# 11_DDR2.net
KiCad netlist of a schematic drawn in Altium Designer
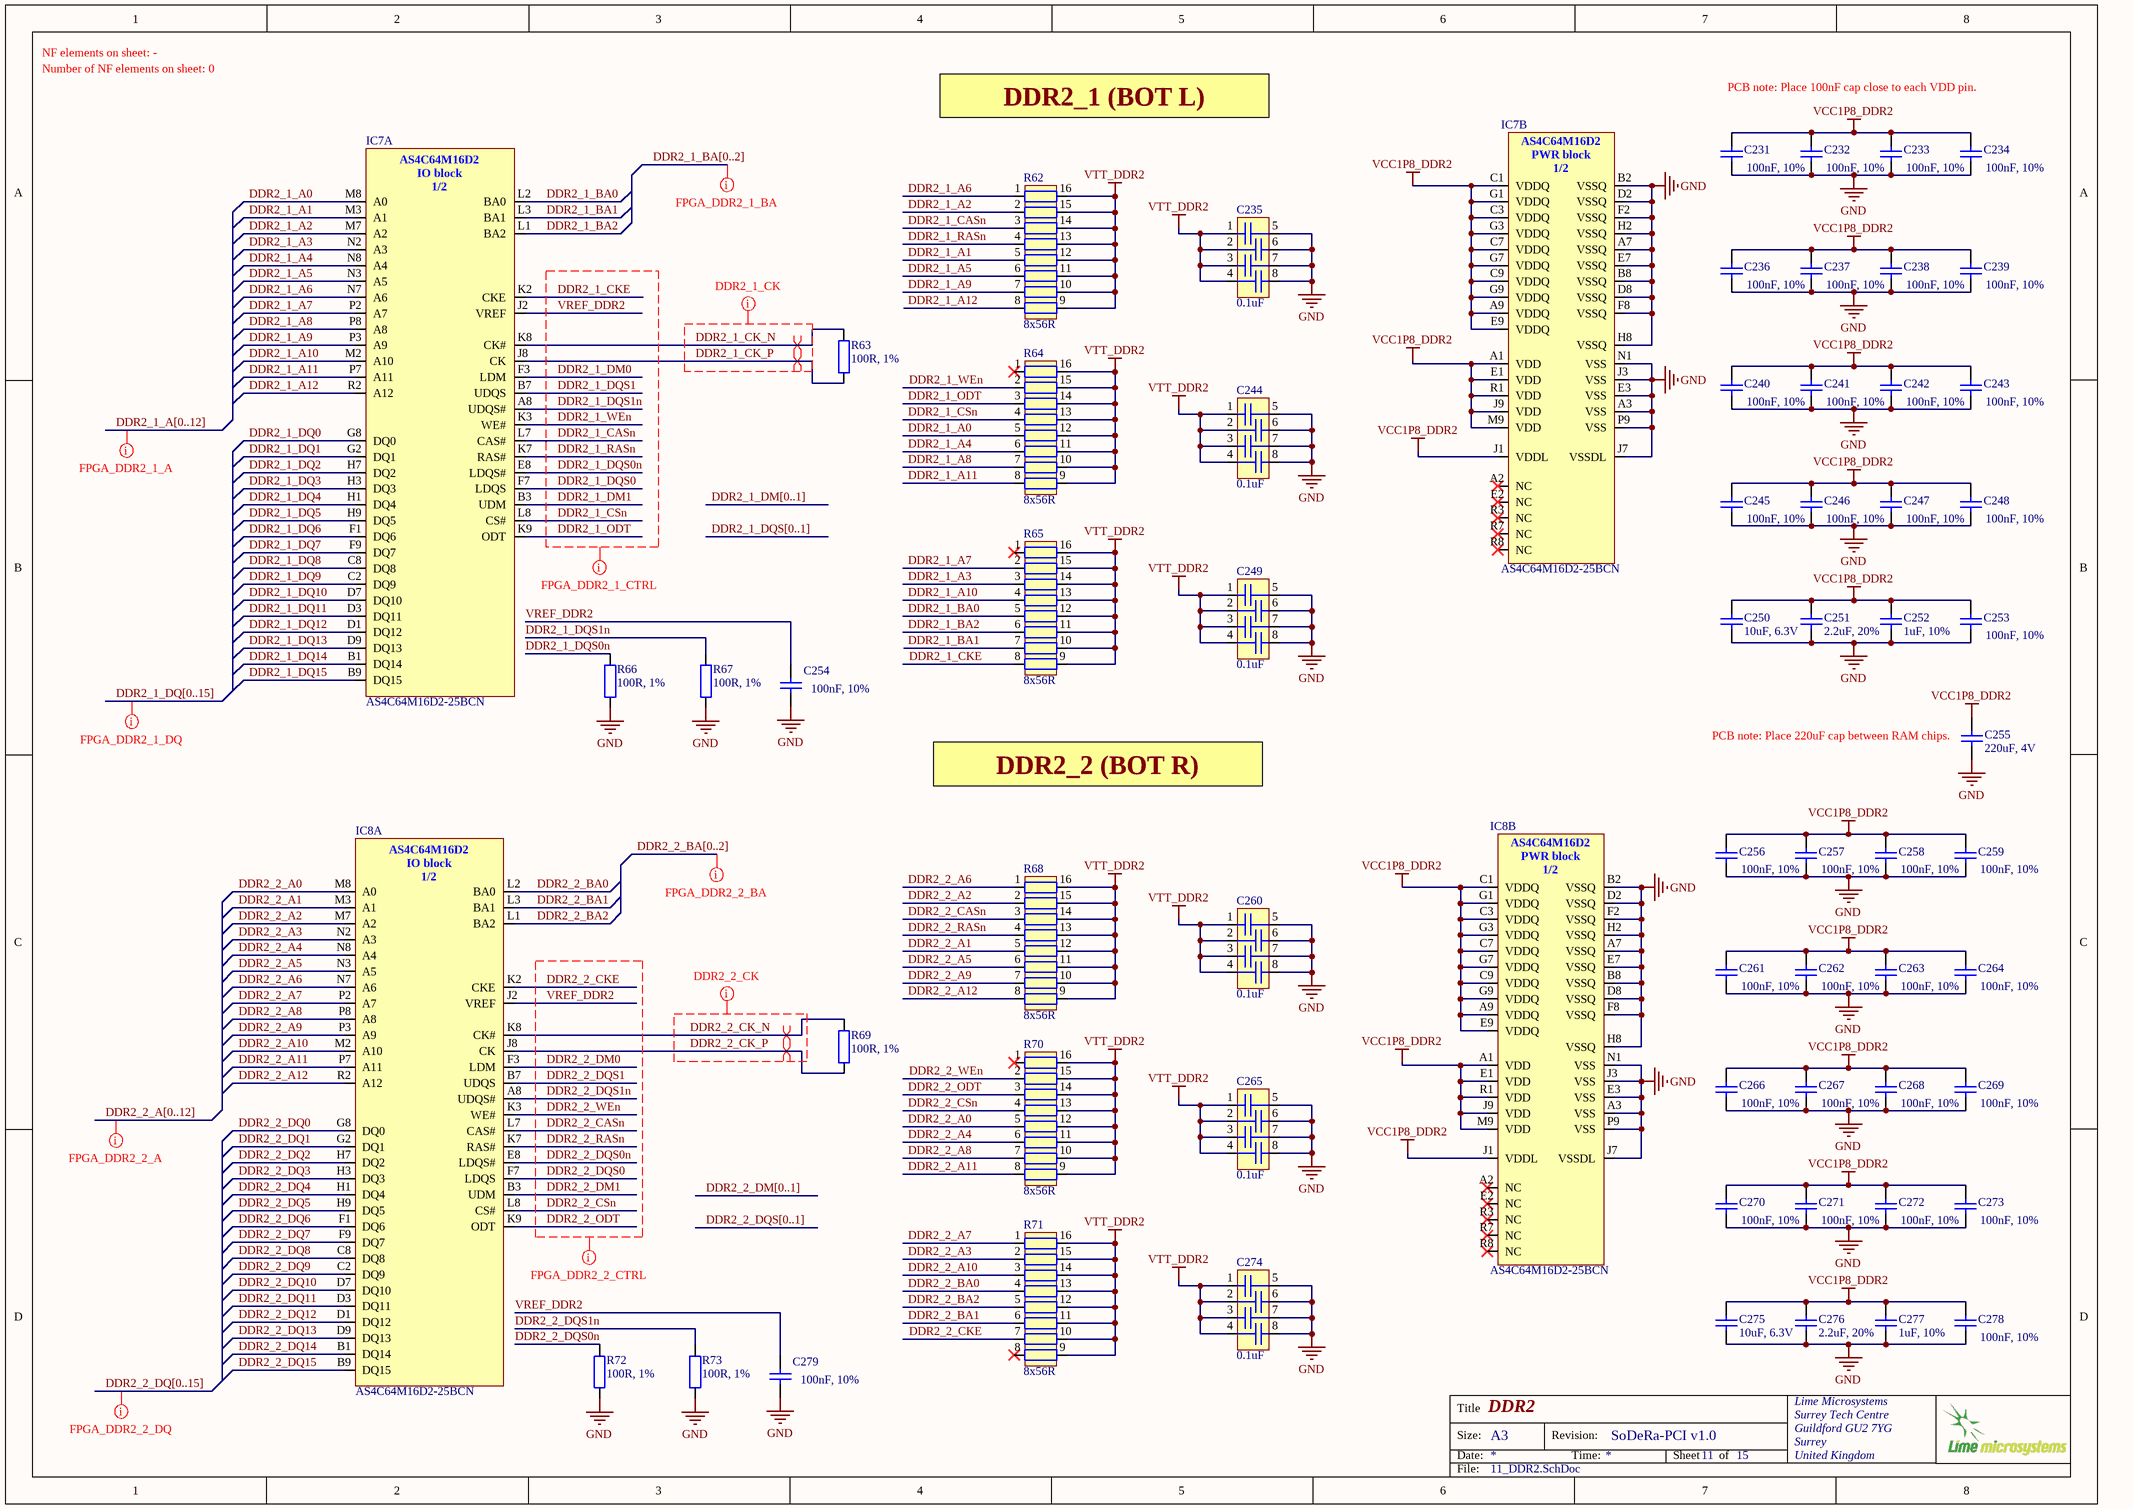
[diagram p0: 11_DDR2.SchDoc]

(export (version "E")
  (design (tool "Eeschema 10.0.6"))
  (components
    (comp (ref "C231")
      (value "100nF, 10%")
      (footprint "LimeMicroAltiumLib_pcbLib:CAP0402")
      (fields
        (field (name "TOLERANCE") "10 %")
        (field (name "MANUFACTURER") "Murata")
        (field (name "MANUFACTURER PART NUMBER") "GRM155R71C104KA88D")
      )
      (libsource (lib "LimeFPGAboard_schLib") (part "Cap_0603"))
    )
    (comp (ref "C232")
      (value "100nF, 10%")
      (footprint "LimeMicroAltiumLib_pcbLib:CAP0402")
      (fields
        (field (name "TOLERANCE") "10 %")
        (field (name "MANUFACTURER") "Murata")
        (field (name "MANUFACTURER PART NUMBER") "GRM155R71C104KA88D")
      )
      (libsource (lib "LimeFPGAboard_schLib") (part "Cap_0603"))
    )
    (comp (ref "C233")
      (value "100nF, 10%")
      (footprint "LimeMicroAltiumLib_pcbLib:CAP0402")
      (fields
        (field (name "TOLERANCE") "10 %")
        (field (name "MANUFACTURER") "Murata")
        (field (name "MANUFACTURER PART NUMBER") "GRM155R71C104KA88D")
      )
      (libsource (lib "LimeFPGAboard_schLib") (part "Cap_0603"))
    )
    (comp (ref "C234")
      (value "100nF, 10%")
      (footprint "LimeMicroAltiumLib_pcbLib:CAP0402")
      (fields
        (field (name "TOLERANCE") "10 %")
        (field (name "MANUFACTURER") "Murata")
        (field (name "MANUFACTURER PART NUMBER") "GRM155R71C104KA88D")
      )
      (libsource (lib "LimeFPGAboard_schLib") (part "Cap_0603"))
    )
    (comp (ref "C235")
      (value "0.1uF")
      (footprint "LimeMicroAltiumLib_pcbLib:CKCA43X7R1C104M100AA")
      (fields (field (name "MANUFACTURER") "TDK") (field (name "TOLERANCE") "20 %"))
      (libsource (lib "LimeFPGAboard_schLib") (part "4X_cap_array_1206"))
    )
    (comp (ref "C236")
      (value "100nF, 10%")
      (footprint "LimeMicroAltiumLib_pcbLib:CAP0402")
      (fields
        (field (name "TOLERANCE") "10 %")
        (field (name "MANUFACTURER") "Murata")
        (field (name "MANUFACTURER PART NUMBER") "GRM155R71C104KA88D")
      )
      (libsource (lib "LimeFPGAboard_schLib") (part "Cap_0603"))
    )
    (comp (ref "C237")
      (value "100nF, 10%")
      (footprint "LimeMicroAltiumLib_pcbLib:CAP0402")
      (fields
        (field (name "TOLERANCE") "10 %")
        (field (name "MANUFACTURER") "Murata")
        (field (name "MANUFACTURER PART NUMBER") "GRM155R71C104KA88D")
      )
      (libsource (lib "LimeFPGAboard_schLib") (part "Cap_0603"))
    )
    (comp (ref "C238")
      (value "100nF, 10%")
      (footprint "LimeMicroAltiumLib_pcbLib:CAP0402")
      (fields
        (field (name "TOLERANCE") "10 %")
        (field (name "MANUFACTURER") "Murata")
        (field (name "MANUFACTURER PART NUMBER") "GRM155R71C104KA88D")
      )
      (libsource (lib "LimeFPGAboard_schLib") (part "Cap_0603"))
    )
    (comp (ref "C239")
      (value "100nF, 10%")
      (footprint "LimeMicroAltiumLib_pcbLib:CAP0402")
      (fields
        (field (name "TOLERANCE") "10 %")
        (field (name "MANUFACTURER") "Murata")
        (field (name "MANUFACTURER PART NUMBER") "GRM155R71C104KA88D")
      )
      (libsource (lib "LimeFPGAboard_schLib") (part "Cap_0603"))
    )
    (comp (ref "C240")
      (value "100nF, 10%")
      (footprint "LimeMicroAltiumLib_pcbLib:CAP0402")
      (fields
        (field (name "TOLERANCE") "10 %")
        (field (name "MANUFACTURER") "Murata")
        (field (name "MANUFACTURER PART NUMBER") "GRM155R71C104KA88D")
      )
      (libsource (lib "LimeFPGAboard_schLib") (part "Cap_0603"))
    )
    (comp (ref "C241")
      (value "100nF, 10%")
      (footprint "LimeMicroAltiumLib_pcbLib:CAP0402")
      (fields
        (field (name "TOLERANCE") "10 %")
        (field (name "MANUFACTURER") "Murata")
        (field (name "MANUFACTURER PART NUMBER") "GRM155R71C104KA88D")
      )
      (libsource (lib "LimeFPGAboard_schLib") (part "Cap_0603"))
    )
    (comp (ref "C242")
      (value "100nF, 10%")
      (footprint "LimeMicroAltiumLib_pcbLib:CAP0402")
      (fields
        (field (name "TOLERANCE") "10 %")
        (field (name "MANUFACTURER") "Murata")
        (field (name "MANUFACTURER PART NUMBER") "GRM155R71C104KA88D")
      )
      (libsource (lib "LimeFPGAboard_schLib") (part "Cap_0603"))
    )
    (comp (ref "C243")
      (value "100nF, 10%")
      (footprint "LimeMicroAltiumLib_pcbLib:CAP0402")
      (fields
        (field (name "TOLERANCE") "10 %")
        (field (name "MANUFACTURER") "Murata")
        (field (name "MANUFACTURER PART NUMBER") "GRM155R71C104KA88D")
      )
      (libsource (lib "LimeFPGAboard_schLib") (part "Cap_0603"))
    )
    (comp (ref "C244")
      (value "0.1uF")
      (footprint "LimeMicroAltiumLib_pcbLib:CKCA43X7R1C104M100AA")
      (fields (field (name "MANUFACTURER") "TDK") (field (name "TOLERANCE") "20 %"))
      (libsource (lib "LimeFPGAboard_schLib") (part "4X_cap_array_1206"))
    )
    (comp (ref "C245")
      (value "100nF, 10%")
      (footprint "LimeMicroAltiumLib_pcbLib:CAP0402")
      (fields
        (field (name "TOLERANCE") "10 %")
        (field (name "MANUFACTURER") "Murata")
        (field (name "MANUFACTURER PART NUMBER") "GRM155R71C104KA88D")
      )
      (libsource (lib "LimeFPGAboard_schLib") (part "Cap_0603"))
    )
    (comp (ref "C246")
      (value "100nF, 10%")
      (footprint "LimeMicroAltiumLib_pcbLib:CAP0402")
      (fields
        (field (name "TOLERANCE") "10 %")
        (field (name "MANUFACTURER") "Murata")
        (field (name "MANUFACTURER PART NUMBER") "GRM155R71C104KA88D")
      )
      (libsource (lib "LimeFPGAboard_schLib") (part "Cap_0603"))
    )
    (comp (ref "C247")
      (value "100nF, 10%")
      (footprint "LimeMicroAltiumLib_pcbLib:CAP0402")
      (fields
        (field (name "TOLERANCE") "10 %")
        (field (name "MANUFACTURER") "Murata")
        (field (name "MANUFACTURER PART NUMBER") "GRM155R71C104KA88D")
      )
      (libsource (lib "LimeFPGAboard_schLib") (part "Cap_0603"))
    )
    (comp (ref "C248")
      (value "100nF, 10%")
      (footprint "LimeMicroAltiumLib_pcbLib:CAP0402")
      (fields
        (field (name "TOLERANCE") "10 %")
        (field (name "MANUFACTURER") "Murata")
        (field (name "MANUFACTURER PART NUMBER") "GRM155R71C104KA88D")
      )
      (libsource (lib "LimeFPGAboard_schLib") (part "Cap_0603"))
    )
    (comp (ref "C249")
      (value "0.1uF")
      (footprint "LimeMicroAltiumLib_pcbLib:CKCA43X7R1C104M100AA")
      (fields (field (name "MANUFACTURER") "TDK") (field (name "TOLERANCE") "20 %"))
      (libsource (lib "LimeFPGAboard_schLib") (part "4X_cap_array_1206"))
    )
    (comp (ref "C250")
      (value "10uF, 6.3V")
      (footprint "LimeMicroAltiumLib_pcbLib:CAP0603")
      (fields (field (name "TOLERANCE") "±20%"))
      (libsource (lib "LimeFPGAboard_schLib") (part "Cap_0603"))
    )
    (comp (ref "C251")
      (value "2.2uF, 20%")
      (footprint "LimeMicroAltiumLib_pcbLib:CAP0402")
      (fields (field (name "MANUFACTURER") "TDK Corporation") (field (name "TOLERANCE") "±20%"))
      (libsource (lib "LimeMicroAltiumLib_schLib") (part "Cap_0402"))
    )
    (comp (ref "C252")
      (value "1uF, 10%")
      (footprint "LimeMicroAltiumLib_pcbLib:CAP0402")
      (fields (field (name "MANUFACTURER") "TDK"))
      (libsource (lib "LimeMicroAltiumLib_schLib") (part "Cap_0402"))
    )
    (comp (ref "C253")
      (value "100nF, 10%")
      (footprint "LimeMicroAltiumLib_pcbLib:CAP0402")
      (fields
        (field (name "TOLERANCE") "10 %")
        (field (name "MANUFACTURER") "Murata")
        (field (name "MANUFACTURER PART NUMBER") "GRM155R71C104KA88D")
      )
      (libsource (lib "LimeFPGAboard_schLib") (part "Cap_0603"))
    )
    (comp (ref "C254")
      (value "100nF, 10%")
      (footprint "LimeMicroAltiumLib_pcbLib:CAP0402")
      (fields
        (field (name "TOLERANCE") "10 %")
        (field (name "MANUFACTURER") "Murata")
        (field (name "MANUFACTURER PART NUMBER") "GRM155R71C104KA88D")
      )
      (libsource (lib "LimeFPGAboard_schLib") (part "Cap_0603"))
    )
    (comp (ref "C255")
      (value "220uF, 4V")
      (footprint "LimeMicroAltiumLib_pcbLib:CAP1206")
      (fields
        (field (name "MANUFACTURER PART NUMBER") "GRM31CR60G227ME11L")
        (field (name "MANUFACTURER") "Murata Electronics North America")
        (field (name "TOLERANCE") "±20%")
      )
      (libsource (lib "LimeFPGAboard_schLib") (part "Cap_1206"))
    )
    (comp (ref "C256")
      (value "100nF, 10%")
      (footprint "LimeMicroAltiumLib_pcbLib:CAP0402")
      (fields
        (field (name "TOLERANCE") "10 %")
        (field (name "MANUFACTURER") "Murata")
        (field (name "MANUFACTURER PART NUMBER") "GRM155R71C104KA88D")
      )
      (libsource (lib "LimeFPGAboard_schLib") (part "Cap_0603"))
    )
    (comp (ref "C257")
      (value "100nF, 10%")
      (footprint "LimeMicroAltiumLib_pcbLib:CAP0402")
      (fields
        (field (name "TOLERANCE") "10 %")
        (field (name "MANUFACTURER") "Murata")
        (field (name "MANUFACTURER PART NUMBER") "GRM155R71C104KA88D")
      )
      (libsource (lib "LimeFPGAboard_schLib") (part "Cap_0603"))
    )
    (comp (ref "C258")
      (value "100nF, 10%")
      (footprint "LimeMicroAltiumLib_pcbLib:CAP0402")
      (fields
        (field (name "TOLERANCE") "10 %")
        (field (name "MANUFACTURER") "Murata")
        (field (name "MANUFACTURER PART NUMBER") "GRM155R71C104KA88D")
      )
      (libsource (lib "LimeFPGAboard_schLib") (part "Cap_0603"))
    )
    (comp (ref "C259")
      (value "100nF, 10%")
      (footprint "LimeMicroAltiumLib_pcbLib:CAP0402")
      (fields
        (field (name "TOLERANCE") "10 %")
        (field (name "MANUFACTURER") "Murata")
        (field (name "MANUFACTURER PART NUMBER") "GRM155R71C104KA88D")
      )
      (libsource (lib "LimeFPGAboard_schLib") (part "Cap_0603"))
    )
    (comp (ref "C260")
      (value "0.1uF")
      (footprint "LimeMicroAltiumLib_pcbLib:CKCA43X7R1C104M100AA")
      (fields (field (name "MANUFACTURER") "TDK") (field (name "TOLERANCE") "20 %"))
      (libsource (lib "LimeFPGAboard_schLib") (part "4X_cap_array_1206"))
    )
    (comp (ref "C261")
      (value "100nF, 10%")
      (footprint "LimeMicroAltiumLib_pcbLib:CAP0402")
      (fields
        (field (name "TOLERANCE") "10 %")
        (field (name "MANUFACTURER") "Murata")
        (field (name "MANUFACTURER PART NUMBER") "GRM155R71C104KA88D")
      )
      (libsource (lib "LimeFPGAboard_schLib") (part "Cap_0603"))
    )
    (comp (ref "C262")
      (value "100nF, 10%")
      (footprint "LimeMicroAltiumLib_pcbLib:CAP0402")
      (fields
        (field (name "TOLERANCE") "10 %")
        (field (name "MANUFACTURER") "Murata")
        (field (name "MANUFACTURER PART NUMBER") "GRM155R71C104KA88D")
      )
      (libsource (lib "LimeFPGAboard_schLib") (part "Cap_0603"))
    )
    (comp (ref "C263")
      (value "100nF, 10%")
      (footprint "LimeMicroAltiumLib_pcbLib:CAP0402")
      (fields
        (field (name "TOLERANCE") "10 %")
        (field (name "MANUFACTURER") "Murata")
        (field (name "MANUFACTURER PART NUMBER") "GRM155R71C104KA88D")
      )
      (libsource (lib "LimeFPGAboard_schLib") (part "Cap_0603"))
    )
    (comp (ref "C264")
      (value "100nF, 10%")
      (footprint "LimeMicroAltiumLib_pcbLib:CAP0402")
      (fields
        (field (name "TOLERANCE") "10 %")
        (field (name "MANUFACTURER") "Murata")
        (field (name "MANUFACTURER PART NUMBER") "GRM155R71C104KA88D")
      )
      (libsource (lib "LimeFPGAboard_schLib") (part "Cap_0603"))
    )
    (comp (ref "C265")
      (value "0.1uF")
      (footprint "LimeMicroAltiumLib_pcbLib:CKCA43X7R1C104M100AA")
      (fields (field (name "MANUFACTURER") "TDK") (field (name "TOLERANCE") "20 %"))
      (libsource (lib "LimeFPGAboard_schLib") (part "4X_cap_array_1206"))
    )
    (comp (ref "C266")
      (value "100nF, 10%")
      (footprint "LimeMicroAltiumLib_pcbLib:CAP0402")
      (fields
        (field (name "TOLERANCE") "10 %")
        (field (name "MANUFACTURER") "Murata")
        (field (name "MANUFACTURER PART NUMBER") "GRM155R71C104KA88D")
      )
      (libsource (lib "LimeFPGAboard_schLib") (part "Cap_0603"))
    )
    (comp (ref "C267")
      (value "100nF, 10%")
      (footprint "LimeMicroAltiumLib_pcbLib:CAP0402")
      (fields
        (field (name "TOLERANCE") "10 %")
        (field (name "MANUFACTURER") "Murata")
        (field (name "MANUFACTURER PART NUMBER") "GRM155R71C104KA88D")
      )
      (libsource (lib "LimeFPGAboard_schLib") (part "Cap_0603"))
    )
    (comp (ref "C268")
      (value "100nF, 10%")
      (footprint "LimeMicroAltiumLib_pcbLib:CAP0402")
      (fields
        (field (name "TOLERANCE") "10 %")
        (field (name "MANUFACTURER") "Murata")
        (field (name "MANUFACTURER PART NUMBER") "GRM155R71C104KA88D")
      )
      (libsource (lib "LimeFPGAboard_schLib") (part "Cap_0603"))
    )
    (comp (ref "C269")
      (value "100nF, 10%")
      (footprint "LimeMicroAltiumLib_pcbLib:CAP0402")
      (fields
        (field (name "TOLERANCE") "10 %")
        (field (name "MANUFACTURER") "Murata")
        (field (name "MANUFACTURER PART NUMBER") "GRM155R71C104KA88D")
      )
      (libsource (lib "LimeFPGAboard_schLib") (part "Cap_0603"))
    )
    (comp (ref "C270")
      (value "100nF, 10%")
      (footprint "LimeMicroAltiumLib_pcbLib:CAP0402")
      (fields
        (field (name "TOLERANCE") "10 %")
        (field (name "MANUFACTURER") "Murata")
        (field (name "MANUFACTURER PART NUMBER") "GRM155R71C104KA88D")
      )
      (libsource (lib "LimeFPGAboard_schLib") (part "Cap_0603"))
    )
    (comp (ref "C271")
      (value "100nF, 10%")
      (footprint "LimeMicroAltiumLib_pcbLib:CAP0402")
      (fields
        (field (name "TOLERANCE") "10 %")
        (field (name "MANUFACTURER") "Murata")
        (field (name "MANUFACTURER PART NUMBER") "GRM155R71C104KA88D")
      )
      (libsource (lib "LimeFPGAboard_schLib") (part "Cap_0603"))
    )
    (comp (ref "C272")
      (value "100nF, 10%")
      (footprint "LimeMicroAltiumLib_pcbLib:CAP0402")
      (fields
        (field (name "TOLERANCE") "10 %")
        (field (name "MANUFACTURER") "Murata")
        (field (name "MANUFACTURER PART NUMBER") "GRM155R71C104KA88D")
      )
      (libsource (lib "LimeFPGAboard_schLib") (part "Cap_0603"))
    )
    (comp (ref "C273")
      (value "100nF, 10%")
      (footprint "LimeMicroAltiumLib_pcbLib:CAP0402")
      (fields
        (field (name "TOLERANCE") "10 %")
        (field (name "MANUFACTURER") "Murata")
        (field (name "MANUFACTURER PART NUMBER") "GRM155R71C104KA88D")
      )
      (libsource (lib "LimeFPGAboard_schLib") (part "Cap_0603"))
    )
    (comp (ref "C274")
      (value "0.1uF")
      (footprint "LimeMicroAltiumLib_pcbLib:CKCA43X7R1C104M100AA")
      (fields (field (name "MANUFACTURER") "TDK") (field (name "TOLERANCE") "20 %"))
      (libsource (lib "LimeFPGAboard_schLib") (part "4X_cap_array_1206"))
    )
    (comp (ref "C275")
      (value "10uF, 6.3V")
      (footprint "LimeMicroAltiumLib_pcbLib:CAP0603")
      (fields (field (name "TOLERANCE") "±20%"))
      (libsource (lib "LimeFPGAboard_schLib") (part "Cap_0603"))
    )
    (comp (ref "C276")
      (value "2.2uF, 20%")
      (footprint "LimeMicroAltiumLib_pcbLib:CAP0402")
      (fields (field (name "MANUFACTURER") "TDK Corporation") (field (name "TOLERANCE") "±20%"))
      (libsource (lib "LimeMicroAltiumLib_schLib") (part "Cap_0402"))
    )
    (comp (ref "C277")
      (value "1uF, 10%")
      (footprint "LimeMicroAltiumLib_pcbLib:CAP0402")
      (fields (field (name "MANUFACTURER") "TDK"))
      (libsource (lib "LimeMicroAltiumLib_schLib") (part "Cap_0402"))
    )
    (comp (ref "C278")
      (value "100nF, 10%")
      (footprint "LimeMicroAltiumLib_pcbLib:CAP0402")
      (fields
        (field (name "TOLERANCE") "10 %")
        (field (name "MANUFACTURER") "Murata")
        (field (name "MANUFACTURER PART NUMBER") "GRM155R71C104KA88D")
      )
      (libsource (lib "LimeFPGAboard_schLib") (part "Cap_0603"))
    )
    (comp (ref "C279")
      (value "100nF, 10%")
      (footprint "LimeMicroAltiumLib_pcbLib:CAP0402")
      (fields
        (field (name "TOLERANCE") "10 %")
        (field (name "MANUFACTURER") "Murata")
        (field (name "MANUFACTURER PART NUMBER") "GRM155R71C104KA88D")
      )
      (libsource (lib "LimeFPGAboard_schLib") (part "Cap_0603"))
    )
    (comp (ref "IC7")
      (value "AS4C64M16D2-25BCN")
      (footprint "LimeMicroAltiumLib_pcbLib:AS4C64M16D2")
      (fields (field (name "MANUFACTURER") "Alliance Memory, Inc."))
      (libsource (lib "LimeMicroAltiumLib_schLib") (part "AS4C64M16D2-25BCN"))
    )
    (comp (ref "IC8")
      (value "AS4C64M16D2-25BCN")
      (footprint "LimeMicroAltiumLib_pcbLib:AS4C64M16D2")
      (fields (field (name "MANUFACTURER") "Alliance Memory, Inc."))
      (libsource (lib "LimeMicroAltiumLib_schLib") (part "AS4C64M16D2-25BCN"))
    )
    (comp (ref "R62")
      (value "8x56R")
      (footprint "LimeMicroAltiumLib_pcbLib:EXB2HV")
      (fields (field (name "MANUFACTURER") "PANASONIC ELECTRONIC COMPONENTS"))
      (libsource (lib "LimeFPGAboard_schLib") (part "8X_resistor_array_0402"))
    )
    (comp (ref "R63")
      (value "100R, 1%")
      (footprint "LimeMicroAltiumLib_pcbLib:RES0402")
      (fields (field (name "TOLERANCE") "±1%"))
      (libsource (lib "LimeFPGAboard_schLib") (part "Res_0402"))
    )
    (comp (ref "R64")
      (value "8x56R")
      (footprint "LimeMicroAltiumLib_pcbLib:EXB2HV")
      (fields (field (name "MANUFACTURER") "PANASONIC ELECTRONIC COMPONENTS"))
      (libsource (lib "LimeFPGAboard_schLib") (part "8X_resistor_array_0402"))
    )
    (comp (ref "R65")
      (value "8x56R")
      (footprint "LimeMicroAltiumLib_pcbLib:EXB2HV")
      (fields (field (name "MANUFACTURER") "PANASONIC ELECTRONIC COMPONENTS"))
      (libsource (lib "LimeFPGAboard_schLib") (part "8X_resistor_array_0402"))
    )
    (comp (ref "R66")
      (value "100R, 1%")
      (footprint "LimeMicroAltiumLib_pcbLib:RES0402")
      (fields (field (name "TOLERANCE") "±1%"))
      (libsource (lib "LimeFPGAboard_schLib") (part "Res_0402"))
    )
    (comp (ref "R67")
      (value "100R, 1%")
      (footprint "LimeMicroAltiumLib_pcbLib:RES0402")
      (fields (field (name "TOLERANCE") "±1%"))
      (libsource (lib "LimeFPGAboard_schLib") (part "Res_0402"))
    )
    (comp (ref "R68")
      (value "8x56R")
      (footprint "LimeMicroAltiumLib_pcbLib:EXB2HV")
      (fields (field (name "MANUFACTURER") "PANASONIC ELECTRONIC COMPONENTS"))
      (libsource (lib "LimeFPGAboard_schLib") (part "8X_resistor_array_0402"))
    )
    (comp (ref "R69")
      (value "100R, 1%")
      (footprint "LimeMicroAltiumLib_pcbLib:RES0402")
      (fields (field (name "TOLERANCE") "±1%"))
      (libsource (lib "LimeFPGAboard_schLib") (part "Res_0402"))
    )
    (comp (ref "R70")
      (value "8x56R")
      (footprint "LimeMicroAltiumLib_pcbLib:EXB2HV")
      (fields (field (name "MANUFACTURER") "PANASONIC ELECTRONIC COMPONENTS"))
      (libsource (lib "LimeFPGAboard_schLib") (part "8X_resistor_array_0402"))
    )
    (comp (ref "R71")
      (value "8x56R")
      (footprint "LimeMicroAltiumLib_pcbLib:EXB2HV")
      (fields (field (name "MANUFACTURER") "PANASONIC ELECTRONIC COMPONENTS"))
      (libsource (lib "LimeFPGAboard_schLib") (part "8X_resistor_array_0402"))
    )
    (comp (ref "R72")
      (value "100R, 1%")
      (footprint "LimeMicroAltiumLib_pcbLib:RES0402")
      (fields (field (name "TOLERANCE") "±1%"))
      (libsource (lib "LimeFPGAboard_schLib") (part "Res_0402"))
    )
    (comp (ref "R73")
      (value "100R, 1%")
      (footprint "LimeMicroAltiumLib_pcbLib:RES0402")
      (fields (field (name "TOLERANCE") "±1%"))
      (libsource (lib "LimeFPGAboard_schLib") (part "Res_0402"))
    )
  )
  (nets
    (net (code "1") (name "/DDR2_1_A0") (class "Default")
      (node (ref "IC7") (pin "M8") (pinfunction "A0_M8") (pintype "passive"))
      (node (ref "R64") (pin "5") (pinfunction "5_5") (pintype "passive"))
    )
    (net (code "2") (name "/DDR2_1_A1") (class "Default")
      (node (ref "IC7") (pin "M3") (pinfunction "A1_M3") (pintype "passive"))
      (node (ref "R62") (pin "5") (pinfunction "5_5") (pintype "passive"))
    )
    (net (code "3") (name "/DDR2_1_A2") (class "Default")
      (node (ref "IC7") (pin "M7") (pinfunction "A2_M7") (pintype "passive"))
      (node (ref "R62") (pin "2") (pinfunction "2_2") (pintype "passive"))
    )
    (net (code "4") (name "/DDR2_1_A3") (class "Default")
      (node (ref "IC7") (pin "N2") (pinfunction "A3_N2") (pintype "passive"))
      (node (ref "R65") (pin "3") (pinfunction "3_3") (pintype "passive"))
    )
    (net (code "5") (name "/DDR2_1_A4") (class "Default")
      (node (ref "IC7") (pin "N8") (pinfunction "A4_N8") (pintype "passive"))
      (node (ref "R64") (pin "6") (pinfunction "6_6") (pintype "passive"))
    )
    (net (code "6") (name "/DDR2_1_A5") (class "Default")
      (node (ref "IC7") (pin "N3") (pinfunction "A5_N3") (pintype "passive"))
      (node (ref "R62") (pin "6") (pinfunction "6_6") (pintype "passive"))
    )
    (net (code "7") (name "/DDR2_1_A6") (class "Default")
      (node (ref "IC7") (pin "N7") (pinfunction "A6_N7") (pintype "passive"))
      (node (ref "R62") (pin "1") (pinfunction "1_1") (pintype "passive"))
    )
    (net (code "8") (name "/DDR2_1_A7") (class "Default")
      (node (ref "IC7") (pin "P2") (pinfunction "A7_P2") (pintype "passive"))
      (node (ref "R65") (pin "2") (pinfunction "2_2") (pintype "passive"))
    )
    (net (code "9") (name "/DDR2_1_A8") (class "Default")
      (node (ref "IC7") (pin "P8") (pinfunction "A8_P8") (pintype "passive"))
      (node (ref "R64") (pin "7") (pinfunction "7_7") (pintype "passive"))
    )
    (net (code "10") (name "/DDR2_1_A9") (class "Default")
      (node (ref "IC7") (pin "P3") (pinfunction "A9_P3") (pintype "passive"))
      (node (ref "R62") (pin "7") (pinfunction "7_7") (pintype "passive"))
    )
    (net (code "11") (name "/DDR2_1_A10") (class "Default")
      (node (ref "IC7") (pin "M2") (pinfunction "A10_M2") (pintype "passive"))
      (node (ref "R65") (pin "4") (pinfunction "4_4") (pintype "passive"))
    )
    (net (code "12") (name "/DDR2_1_A11") (class "Default")
      (node (ref "IC7") (pin "P7") (pinfunction "A11_P7") (pintype "passive"))
      (node (ref "R64") (pin "8") (pinfunction "8_8") (pintype "passive"))
    )
    (net (code "13") (name "/DDR2_1_A12") (class "Default")
      (node (ref "IC7") (pin "R2") (pinfunction "A12_R2") (pintype "passive"))
      (node (ref "R62") (pin "8") (pinfunction "8_8") (pintype "passive"))
    )
    (net (code "15") (name "/DDR2_1_BA0") (class "Default")
      (node (ref "IC7") (pin "L2") (pinfunction "BA0_L2") (pintype "passive"))
      (node (ref "R65") (pin "5") (pinfunction "5_5") (pintype "passive"))
    )
    (net (code "16") (name "/DDR2_1_BA1") (class "Default")
      (node (ref "IC7") (pin "L3") (pinfunction "BA1_L3") (pintype "passive"))
      (node (ref "R65") (pin "7") (pinfunction "7_7") (pintype "passive"))
    )
    (net (code "17") (name "/DDR2_1_BA2") (class "Default")
      (node (ref "IC7") (pin "L1") (pinfunction "BA2_L1") (pintype "passive"))
      (node (ref "R65") (pin "6") (pinfunction "6_6") (pintype "passive"))
    )
    (net (code "19") (name "/DDR2_1_CASn") (class "Default")
      (node (ref "IC7") (pin "L7") (pinfunction "CAS#_L7") (pintype "passive"))
      (node (ref "R62") (pin "3") (pinfunction "3_3") (pintype "passive"))
    )
    (net (code "20") (name "/DDR2_1_CKE") (class "Default")
      (node (ref "IC7") (pin "K2") (pinfunction "CKE_K2") (pintype "passive"))
      (node (ref "R65") (pin "8") (pinfunction "8_8") (pintype "passive"))
    )
    (net (code "21") (name "/DDR2_1_CK_N") (class "Default")
      (node (ref "IC7") (pin "K8") (pinfunction "CK#_K8") (pintype "passive"))
      (node (ref "R63") (pin "2") (pinfunction "2_2") (pintype "passive"))
    )
    (net (code "22") (name "/DDR2_1_CK_P") (class "Default")
      (node (ref "IC7") (pin "J8") (pinfunction "CK_J8") (pintype "passive"))
      (node (ref "R63") (pin "1") (pinfunction "1_1") (pintype "passive"))
    )
    (net (code "23") (name "/DDR2_1_CSn") (class "Default")
      (node (ref "IC7") (pin "L8") (pinfunction "CS#_L8") (pintype "passive"))
      (node (ref "R64") (pin "4") (pinfunction "4_4") (pintype "passive"))
    )
    (net (code "24") (name "/DDR2_1_DM0") (class "Default")
      (node (ref "IC7") (pin "F3") (pinfunction "LDM_F3") (pintype "passive"))
    )
    (net (code "25") (name "/DDR2_1_DM1") (class "Default")
      (node (ref "IC7") (pin "B3") (pinfunction "UDM_B3") (pintype "passive"))
    )
    (net (code "27") (name "/DDR2_1_DQ0") (class "Default")
      (node (ref "IC7") (pin "G8") (pinfunction "DQ0_G8") (pintype "passive"))
    )
    (net (code "28") (name "/DDR2_1_DQ1") (class "Default")
      (node (ref "IC7") (pin "G2") (pinfunction "DQ1_G2") (pintype "passive"))
    )
    (net (code "29") (name "/DDR2_1_DQ2") (class "Default")
      (node (ref "IC7") (pin "H7") (pinfunction "DQ2_H7") (pintype "passive"))
    )
    (net (code "30") (name "/DDR2_1_DQ3") (class "Default")
      (node (ref "IC7") (pin "H3") (pinfunction "DQ3_H3") (pintype "passive"))
    )
    (net (code "31") (name "/DDR2_1_DQ4") (class "Default")
      (node (ref "IC7") (pin "H1") (pinfunction "DQ4_H1") (pintype "passive"))
    )
    (net (code "32") (name "/DDR2_1_DQ5") (class "Default")
      (node (ref "IC7") (pin "H9") (pinfunction "DQ5_H9") (pintype "passive"))
    )
    (net (code "33") (name "/DDR2_1_DQ6") (class "Default")
      (node (ref "IC7") (pin "F1") (pinfunction "DQ6_F1") (pintype "passive"))
    )
    (net (code "34") (name "/DDR2_1_DQ7") (class "Default")
      (node (ref "IC7") (pin "F9") (pinfunction "DQ7_F9") (pintype "passive"))
    )
    (net (code "35") (name "/DDR2_1_DQ8") (class "Default")
      (node (ref "IC7") (pin "C8") (pinfunction "DQ8_C8") (pintype "passive"))
    )
    (net (code "36") (name "/DDR2_1_DQ9") (class "Default")
      (node (ref "IC7") (pin "C2") (pinfunction "DQ9_C2") (pintype "passive"))
    )
    (net (code "37") (name "/DDR2_1_DQ10") (class "Default")
      (node (ref "IC7") (pin "D7") (pinfunction "DQ10_D7") (pintype "passive"))
    )
    (net (code "38") (name "/DDR2_1_DQ11") (class "Default")
      (node (ref "IC7") (pin "D3") (pinfunction "DQ11_D3") (pintype "passive"))
    )
    (net (code "39") (name "/DDR2_1_DQ12") (class "Default")
      (node (ref "IC7") (pin "D1") (pinfunction "DQ12_D1") (pintype "passive"))
    )
    (net (code "40") (name "/DDR2_1_DQ13") (class "Default")
      (node (ref "IC7") (pin "D9") (pinfunction "DQ13_D9") (pintype "passive"))
    )
    (net (code "41") (name "/DDR2_1_DQ14") (class "Default")
      (node (ref "IC7") (pin "B1") (pinfunction "DQ14_B1") (pintype "passive"))
    )
    (net (code "42") (name "/DDR2_1_DQ15") (class "Default")
      (node (ref "IC7") (pin "B9") (pinfunction "DQ15_B9") (pintype "passive"))
    )
    (net (code "43") (name "/DDR2_1_DQS0") (class "Default")
      (node (ref "IC7") (pin "F7") (pinfunction "LDQS_F7") (pintype "passive"))
    )
    (net (code "44") (name "/DDR2_1_DQS0n") (class "Default")
      (node (ref "IC7") (pin "E8") (pinfunction "LDQS#_E8") (pintype "passive"))
      (node (ref "R66") (pin "2") (pinfunction "2_2") (pintype "passive"))
    )
    (net (code "45") (name "/DDR2_1_DQS1") (class "Default")
      (node (ref "IC7") (pin "B7") (pinfunction "UDQS_B7") (pintype "passive"))
    )
    (net (code "46") (name "/DDR2_1_DQS1n") (class "Default")
      (node (ref "IC7") (pin "A8") (pinfunction "UDQS#_A8") (pintype "passive"))
      (node (ref "R67") (pin "2") (pinfunction "2_2") (pintype "passive"))
    )
    (net (code "49") (name "/DDR2_1_ODT") (class "Default")
      (node (ref "IC7") (pin "K9") (pinfunction "ODT_K9") (pintype "passive"))
      (node (ref "R64") (pin "3") (pinfunction "3_3") (pintype "passive"))
    )
    (net (code "50") (name "/DDR2_1_RASn") (class "Default")
      (node (ref "IC7") (pin "K7") (pinfunction "RAS#_K7") (pintype "passive"))
      (node (ref "R62") (pin "4") (pinfunction "4_4") (pintype "passive"))
    )
    (net (code "51") (name "/DDR2_1_WEn") (class "Default")
      (node (ref "IC7") (pin "K3") (pinfunction "WE#_K3") (pintype "passive"))
      (node (ref "R64") (pin "2") (pinfunction "2_2") (pintype "passive"))
    )
    (net (code "52") (name "/DDR2_2_A0") (class "Default")
      (node (ref "IC8") (pin "M8") (pinfunction "A0_M8") (pintype "passive"))
      (node (ref "R70") (pin "5") (pinfunction "5_5") (pintype "passive"))
    )
    (net (code "53") (name "/DDR2_2_A1") (class "Default")
      (node (ref "IC8") (pin "M3") (pinfunction "A1_M3") (pintype "passive"))
      (node (ref "R68") (pin "5") (pinfunction "5_5") (pintype "passive"))
    )
    (net (code "54") (name "/DDR2_2_A2") (class "Default")
      (node (ref "IC8") (pin "M7") (pinfunction "A2_M7") (pintype "passive"))
      (node (ref "R68") (pin "2") (pinfunction "2_2") (pintype "passive"))
    )
    (net (code "55") (name "/DDR2_2_A3") (class "Default")
      (node (ref "IC8") (pin "N2") (pinfunction "A3_N2") (pintype "passive"))
      (node (ref "R71") (pin "2") (pinfunction "2_2") (pintype "passive"))
    )
    (net (code "56") (name "/DDR2_2_A4") (class "Default")
      (node (ref "IC8") (pin "N8") (pinfunction "A4_N8") (pintype "passive"))
      (node (ref "R70") (pin "6") (pinfunction "6_6") (pintype "passive"))
    )
    (net (code "57") (name "/DDR2_2_A5") (class "Default")
      (node (ref "IC8") (pin "N3") (pinfunction "A5_N3") (pintype "passive"))
      (node (ref "R68") (pin "6") (pinfunction "6_6") (pintype "passive"))
    )
    (net (code "58") (name "/DDR2_2_A6") (class "Default")
      (node (ref "IC8") (pin "N7") (pinfunction "A6_N7") (pintype "passive"))
      (node (ref "R68") (pin "1") (pinfunction "1_1") (pintype "passive"))
    )
    (net (code "59") (name "/DDR2_2_A7") (class "Default")
      (node (ref "IC8") (pin "P2") (pinfunction "A7_P2") (pintype "passive"))
      (node (ref "R71") (pin "1") (pinfunction "1_1") (pintype "passive"))
    )
    (net (code "60") (name "/DDR2_2_A8") (class "Default")
      (node (ref "IC8") (pin "P8") (pinfunction "A8_P8") (pintype "passive"))
      (node (ref "R70") (pin "7") (pinfunction "7_7") (pintype "passive"))
    )
    (net (code "61") (name "/DDR2_2_A9") (class "Default")
      (node (ref "IC8") (pin "P3") (pinfunction "A9_P3") (pintype "passive"))
      (node (ref "R68") (pin "7") (pinfunction "7_7") (pintype "passive"))
    )
    (net (code "62") (name "/DDR2_2_A10") (class "Default")
      (node (ref "IC8") (pin "M2") (pinfunction "A10_M2") (pintype "passive"))
      (node (ref "R71") (pin "3") (pinfunction "3_3") (pintype "passive"))
    )
    (net (code "63") (name "/DDR2_2_A11") (class "Default")
      (node (ref "IC8") (pin "P7") (pinfunction "A11_P7") (pintype "passive"))
      (node (ref "R70") (pin "8") (pinfunction "8_8") (pintype "passive"))
    )
    (net (code "64") (name "/DDR2_2_A12") (class "Default")
      (node (ref "IC8") (pin "R2") (pinfunction "A12_R2") (pintype "passive"))
      (node (ref "R68") (pin "8") (pinfunction "8_8") (pintype "passive"))
    )
    (net (code "66") (name "/DDR2_2_BA0") (class "Default")
      (node (ref "IC8") (pin "L2") (pinfunction "BA0_L2") (pintype "passive"))
      (node (ref "R71") (pin "4") (pinfunction "4_4") (pintype "passive"))
    )
    (net (code "67") (name "/DDR2_2_BA1") (class "Default")
      (node (ref "IC8") (pin "L3") (pinfunction "BA1_L3") (pintype "passive"))
      (node (ref "R71") (pin "6") (pinfunction "6_6") (pintype "passive"))
    )
    (net (code "68") (name "/DDR2_2_BA2") (class "Default")
      (node (ref "IC8") (pin "L1") (pinfunction "BA2_L1") (pintype "passive"))
      (node (ref "R71") (pin "5") (pinfunction "5_5") (pintype "passive"))
    )
    (net (code "70") (name "/DDR2_2_CASn") (class "Default")
      (node (ref "IC8") (pin "L7") (pinfunction "CAS#_L7") (pintype "passive"))
      (node (ref "R68") (pin "3") (pinfunction "3_3") (pintype "passive"))
    )
    (net (code "71") (name "/DDR2_2_CKE") (class "Default")
      (node (ref "IC8") (pin "K2") (pinfunction "CKE_K2") (pintype "passive"))
      (node (ref "R71") (pin "7") (pinfunction "7_7") (pintype "passive"))
    )
    (net (code "72") (name "/DDR2_2_CK_N") (class "Default")
      (node (ref "IC8") (pin "K8") (pinfunction "CK#_K8") (pintype "passive"))
      (node (ref "R69") (pin "2") (pinfunction "2_2") (pintype "passive"))
    )
    (net (code "73") (name "/DDR2_2_CK_P") (class "Default")
      (node (ref "IC8") (pin "J8") (pinfunction "CK_J8") (pintype "passive"))
      (node (ref "R69") (pin "1") (pinfunction "1_1") (pintype "passive"))
    )
    (net (code "74") (name "/DDR2_2_CSn") (class "Default")
      (node (ref "IC8") (pin "L8") (pinfunction "CS#_L8") (pintype "passive"))
      (node (ref "R70") (pin "4") (pinfunction "4_4") (pintype "passive"))
    )
    (net (code "75") (name "/DDR2_2_DM0") (class "Default")
      (node (ref "IC8") (pin "F3") (pinfunction "LDM_F3") (pintype "passive"))
    )
    (net (code "76") (name "/DDR2_2_DM1") (class "Default")
      (node (ref "IC8") (pin "B3") (pinfunction "UDM_B3") (pintype "passive"))
    )
    (net (code "78") (name "/DDR2_2_DQ0") (class "Default")
      (node (ref "IC8") (pin "G8") (pinfunction "DQ0_G8") (pintype "passive"))
    )
    (net (code "79") (name "/DDR2_2_DQ1") (class "Default")
      (node (ref "IC8") (pin "G2") (pinfunction "DQ1_G2") (pintype "passive"))
    )
    (net (code "80") (name "/DDR2_2_DQ2") (class "Default")
      (node (ref "IC8") (pin "H7") (pinfunction "DQ2_H7") (pintype "passive"))
    )
    (net (code "81") (name "/DDR2_2_DQ3") (class "Default")
      (node (ref "IC8") (pin "H3") (pinfunction "DQ3_H3") (pintype "passive"))
    )
    (net (code "82") (name "/DDR2_2_DQ4") (class "Default")
      (node (ref "IC8") (pin "H1") (pinfunction "DQ4_H1") (pintype "passive"))
    )
    (net (code "83") (name "/DDR2_2_DQ5") (class "Default")
      (node (ref "IC8") (pin "H9") (pinfunction "DQ5_H9") (pintype "passive"))
    )
    (net (code "84") (name "/DDR2_2_DQ6") (class "Default")
      (node (ref "IC8") (pin "F1") (pinfunction "DQ6_F1") (pintype "passive"))
    )
    (net (code "85") (name "/DDR2_2_DQ7") (class "Default")
      (node (ref "IC8") (pin "F9") (pinfunction "DQ7_F9") (pintype "passive"))
    )
    (net (code "86") (name "/DDR2_2_DQ8") (class "Default")
      (node (ref "IC8") (pin "C8") (pinfunction "DQ8_C8") (pintype "passive"))
    )
    (net (code "87") (name "/DDR2_2_DQ9") (class "Default")
      (node (ref "IC8") (pin "C2") (pinfunction "DQ9_C2") (pintype "passive"))
    )
    (net (code "88") (name "/DDR2_2_DQ10") (class "Default")
      (node (ref "IC8") (pin "D7") (pinfunction "DQ10_D7") (pintype "passive"))
    )
    (net (code "89") (name "/DDR2_2_DQ11") (class "Default")
      (node (ref "IC8") (pin "D3") (pinfunction "DQ11_D3") (pintype "passive"))
    )
    (net (code "90") (name "/DDR2_2_DQ12") (class "Default")
      (node (ref "IC8") (pin "D1") (pinfunction "DQ12_D1") (pintype "passive"))
    )
    (net (code "91") (name "/DDR2_2_DQ13") (class "Default")
      (node (ref "IC8") (pin "D9") (pinfunction "DQ13_D9") (pintype "passive"))
    )
    (net (code "92") (name "/DDR2_2_DQ14") (class "Default")
      (node (ref "IC8") (pin "B1") (pinfunction "DQ14_B1") (pintype "passive"))
    )
    (net (code "93") (name "/DDR2_2_DQ15") (class "Default")
      (node (ref "IC8") (pin "B9") (pinfunction "DQ15_B9") (pintype "passive"))
    )
    (net (code "94") (name "/DDR2_2_DQS0") (class "Default")
      (node (ref "IC8") (pin "F7") (pinfunction "LDQS_F7") (pintype "passive"))
    )
    (net (code "95") (name "/DDR2_2_DQS0n") (class "Default")
      (node (ref "IC8") (pin "E8") (pinfunction "LDQS#_E8") (pintype "passive"))
      (node (ref "R72") (pin "2") (pinfunction "2_2") (pintype "passive"))
    )
    (net (code "96") (name "/DDR2_2_DQS1") (class "Default")
      (node (ref "IC8") (pin "B7") (pinfunction "UDQS_B7") (pintype "passive"))
    )
    (net (code "97") (name "/DDR2_2_DQS1n") (class "Default")
      (node (ref "IC8") (pin "A8") (pinfunction "UDQS#_A8") (pintype "passive"))
      (node (ref "R73") (pin "2") (pinfunction "2_2") (pintype "passive"))
    )
    (net (code "100") (name "/DDR2_2_ODT") (class "Default")
      (node (ref "IC8") (pin "K9") (pinfunction "ODT_K9") (pintype "passive"))
      (node (ref "R70") (pin "3") (pinfunction "3_3") (pintype "passive"))
    )
    (net (code "101") (name "/DDR2_2_RASn") (class "Default")
      (node (ref "IC8") (pin "K7") (pinfunction "RAS#_K7") (pintype "passive"))
      (node (ref "R68") (pin "4") (pinfunction "4_4") (pintype "passive"))
    )
    (net (code "102") (name "/DDR2_2_WEn") (class "Default")
      (node (ref "IC8") (pin "K3") (pinfunction "WE#_K3") (pintype "passive"))
      (node (ref "R70") (pin "2") (pinfunction "2_2") (pintype "passive"))
    )
    (net (code "103") (name "/VREF_DDR2") (class "Default")
      (node (ref "C254") (pin "1") (pinfunction "1_1") (pintype "passive"))
      (node (ref "C279") (pin "1") (pinfunction "1_1") (pintype "passive"))
      (node (ref "IC7") (pin "J2") (pinfunction "VREF_J2") (pintype "passive"))
      (node (ref "IC8") (pin "J2") (pinfunction "VREF_J2") (pintype "passive"))
    )
    (net (code "104") (name "GND") (class "Default")
      (node (ref "C231") (pin "2") (pinfunction "2_2") (pintype "passive"))
      (node (ref "C232") (pin "2") (pinfunction "2_2") (pintype "passive"))
      (node (ref "C233") (pin "2") (pinfunction "2_2") (pintype "passive"))
      (node (ref "C234") (pin "2") (pinfunction "2_2") (pintype "passive"))
      (node (ref "C235") (pin "5") (pinfunction "5_5") (pintype "passive"))
      (node (ref "C235") (pin "6") (pinfunction "6_6") (pintype "passive"))
      (node (ref "C235") (pin "7") (pinfunction "7_7") (pintype "passive"))
      (node (ref "C235") (pin "8") (pinfunction "8_8") (pintype "passive"))
      (node (ref "C236") (pin "2") (pinfunction "2_2") (pintype "passive"))
      (node (ref "C237") (pin "2") (pinfunction "2_2") (pintype "passive"))
      (node (ref "C238") (pin "2") (pinfunction "2_2") (pintype "passive"))
      (node (ref "C239") (pin "2") (pinfunction "2_2") (pintype "passive"))
      (node (ref "C240") (pin "2") (pinfunction "2_2") (pintype "passive"))
      (node (ref "C241") (pin "2") (pinfunction "2_2") (pintype "passive"))
      (node (ref "C242") (pin "2") (pinfunction "2_2") (pintype "passive"))
      (node (ref "C243") (pin "2") (pinfunction "2_2") (pintype "passive"))
      (node (ref "C244") (pin "5") (pinfunction "5_5") (pintype "passive"))
      (node (ref "C244") (pin "6") (pinfunction "6_6") (pintype "passive"))
      (node (ref "C244") (pin "7") (pinfunction "7_7") (pintype "passive"))
      (node (ref "C244") (pin "8") (pinfunction "8_8") (pintype "passive"))
      (node (ref "C245") (pin "2") (pinfunction "2_2") (pintype "passive"))
      (node (ref "C246") (pin "2") (pinfunction "2_2") (pintype "passive"))
      (node (ref "C247") (pin "2") (pinfunction "2_2") (pintype "passive"))
      (node (ref "C248") (pin "2") (pinfunction "2_2") (pintype "passive"))
      (node (ref "C249") (pin "5") (pinfunction "5_5") (pintype "passive"))
      (node (ref "C249") (pin "6") (pinfunction "6_6") (pintype "passive"))
      (node (ref "C249") (pin "7") (pinfunction "7_7") (pintype "passive"))
      (node (ref "C249") (pin "8") (pinfunction "8_8") (pintype "passive"))
      (node (ref "C250") (pin "1") (pinfunction "1_1") (pintype "passive"))
      (node (ref "C251") (pin "1") (pinfunction "1_1") (pintype "passive"))
      (node (ref "C252") (pin "1") (pinfunction "1_1") (pintype "passive"))
      (node (ref "C253") (pin "2") (pinfunction "2_2") (pintype "passive"))
      (node (ref "C254") (pin "2") (pinfunction "2_2") (pintype "passive"))
      (node (ref "C255") (pin "1") (pinfunction "1_1") (pintype "passive"))
      (node (ref "C256") (pin "2") (pinfunction "2_2") (pintype "passive"))
      (node (ref "C257") (pin "2") (pinfunction "2_2") (pintype "passive"))
      (node (ref "C258") (pin "2") (pinfunction "2_2") (pintype "passive"))
      (node (ref "C259") (pin "2") (pinfunction "2_2") (pintype "passive"))
      (node (ref "C260") (pin "5") (pinfunction "5_5") (pintype "passive"))
      (node (ref "C260") (pin "6") (pinfunction "6_6") (pintype "passive"))
      (node (ref "C260") (pin "7") (pinfunction "7_7") (pintype "passive"))
      (node (ref "C260") (pin "8") (pinfunction "8_8") (pintype "passive"))
      (node (ref "C261") (pin "2") (pinfunction "2_2") (pintype "passive"))
      (node (ref "C262") (pin "2") (pinfunction "2_2") (pintype "passive"))
      (node (ref "C263") (pin "2") (pinfunction "2_2") (pintype "passive"))
      (node (ref "C264") (pin "2") (pinfunction "2_2") (pintype "passive"))
      (node (ref "C265") (pin "5") (pinfunction "5_5") (pintype "passive"))
      (node (ref "C265") (pin "6") (pinfunction "6_6") (pintype "passive"))
      (node (ref "C265") (pin "7") (pinfunction "7_7") (pintype "passive"))
      (node (ref "C265") (pin "8") (pinfunction "8_8") (pintype "passive"))
      (node (ref "C266") (pin "2") (pinfunction "2_2") (pintype "passive"))
      (node (ref "C267") (pin "2") (pinfunction "2_2") (pintype "passive"))
      (node (ref "C268") (pin "2") (pinfunction "2_2") (pintype "passive"))
      (node (ref "C269") (pin "2") (pinfunction "2_2") (pintype "passive"))
      (node (ref "C270") (pin "2") (pinfunction "2_2") (pintype "passive"))
      (node (ref "C271") (pin "2") (pinfunction "2_2") (pintype "passive"))
      (node (ref "C272") (pin "2") (pinfunction "2_2") (pintype "passive"))
      (node (ref "C273") (pin "2") (pinfunction "2_2") (pintype "passive"))
      (node (ref "C274") (pin "5") (pinfunction "5_5") (pintype "passive"))
      (node (ref "C274") (pin "6") (pinfunction "6_6") (pintype "passive"))
      (node (ref "C274") (pin "7") (pinfunction "7_7") (pintype "passive"))
      (node (ref "C274") (pin "8") (pinfunction "8_8") (pintype "passive"))
      (node (ref "C275") (pin "1") (pinfunction "1_1") (pintype "passive"))
      (node (ref "C276") (pin "1") (pinfunction "1_1") (pintype "passive"))
      (node (ref "C277") (pin "1") (pinfunction "1_1") (pintype "passive"))
      (node (ref "C278") (pin "2") (pinfunction "2_2") (pintype "passive"))
      (node (ref "C279") (pin "2") (pinfunction "2_2") (pintype "passive"))
      (node (ref "IC7") (pin "A3") (pinfunction "VSS_A3") (pintype "power_in"))
      (node (ref "IC7") (pin "A7") (pinfunction "VSSQ_A7") (pintype "power_in"))
      (node (ref "IC7") (pin "B2") (pinfunction "VSSQ_B2") (pintype "power_in"))
      (node (ref "IC7") (pin "B8") (pinfunction "VSSQ_B8") (pintype "power_in"))
      (node (ref "IC7") (pin "D2") (pinfunction "VSSQ_D2") (pintype "power_in"))
      (node (ref "IC7") (pin "D8") (pinfunction "VSSQ_D8") (pintype "power_in"))
      (node (ref "IC7") (pin "E3") (pinfunction "VSS_E3") (pintype "power_in"))
      (node (ref "IC7") (pin "E7") (pinfunction "VSSQ_E7") (pintype "power_in"))
      (node (ref "IC7") (pin "F2") (pinfunction "VSSQ_F2") (pintype "power_in"))
      (node (ref "IC7") (pin "F8") (pinfunction "VSSQ_F8") (pintype "power_in"))
      (node (ref "IC7") (pin "H2") (pinfunction "VSSQ_H2") (pintype "power_in"))
      (node (ref "IC7") (pin "H8") (pinfunction "VSSQ_H8") (pintype "power_in"))
      (node (ref "IC7") (pin "J3") (pinfunction "VSS_J3") (pintype "power_in"))
      (node (ref "IC7") (pin "J7") (pinfunction "VSSDL_J7") (pintype "power_in"))
      (node (ref "IC7") (pin "N1") (pinfunction "VSS_N1") (pintype "power_in"))
      (node (ref "IC7") (pin "P9") (pinfunction "VSS_P9") (pintype "power_in"))
      (node (ref "IC8") (pin "A3") (pinfunction "VSS_A3") (pintype "power_in"))
      (node (ref "IC8") (pin "A7") (pinfunction "VSSQ_A7") (pintype "power_in"))
      (node (ref "IC8") (pin "B2") (pinfunction "VSSQ_B2") (pintype "power_in"))
      (node (ref "IC8") (pin "B8") (pinfunction "VSSQ_B8") (pintype "power_in"))
      (node (ref "IC8") (pin "D2") (pinfunction "VSSQ_D2") (pintype "power_in"))
      (node (ref "IC8") (pin "D8") (pinfunction "VSSQ_D8") (pintype "power_in"))
      (node (ref "IC8") (pin "E3") (pinfunction "VSS_E3") (pintype "power_in"))
      (node (ref "IC8") (pin "E7") (pinfunction "VSSQ_E7") (pintype "power_in"))
      (node (ref "IC8") (pin "F2") (pinfunction "VSSQ_F2") (pintype "power_in"))
      (node (ref "IC8") (pin "F8") (pinfunction "VSSQ_F8") (pintype "power_in"))
      (node (ref "IC8") (pin "H2") (pinfunction "VSSQ_H2") (pintype "power_in"))
      (node (ref "IC8") (pin "H8") (pinfunction "VSSQ_H8") (pintype "power_in"))
      (node (ref "IC8") (pin "J3") (pinfunction "VSS_J3") (pintype "power_in"))
      (node (ref "IC8") (pin "J7") (pinfunction "VSSDL_J7") (pintype "power_in"))
      (node (ref "IC8") (pin "N1") (pinfunction "VSS_N1") (pintype "power_in"))
      (node (ref "IC8") (pin "P9") (pinfunction "VSS_P9") (pintype "power_in"))
      (node (ref "R66") (pin "1") (pinfunction "1_1") (pintype "passive"))
      (node (ref "R67") (pin "1") (pinfunction "1_1") (pintype "passive"))
      (node (ref "R72") (pin "1") (pinfunction "1_1") (pintype "passive"))
      (node (ref "R73") (pin "1") (pinfunction "1_1") (pintype "passive"))
    )
    (net (code "105") (name "VCC1P8_DDR2") (class "Default")
      (node (ref "C231") (pin "1") (pinfunction "1_1") (pintype "passive"))
      (node (ref "C232") (pin "1") (pinfunction "1_1") (pintype "passive"))
      (node (ref "C233") (pin "1") (pinfunction "1_1") (pintype "passive"))
      (node (ref "C234") (pin "1") (pinfunction "1_1") (pintype "passive"))
      (node (ref "C236") (pin "1") (pinfunction "1_1") (pintype "passive"))
      (node (ref "C237") (pin "1") (pinfunction "1_1") (pintype "passive"))
      (node (ref "C238") (pin "1") (pinfunction "1_1") (pintype "passive"))
      (node (ref "C239") (pin "1") (pinfunction "1_1") (pintype "passive"))
      (node (ref "C240") (pin "1") (pinfunction "1_1") (pintype "passive"))
      (node (ref "C241") (pin "1") (pinfunction "1_1") (pintype "passive"))
      (node (ref "C242") (pin "1") (pinfunction "1_1") (pintype "passive"))
      (node (ref "C243") (pin "1") (pinfunction "1_1") (pintype "passive"))
      (node (ref "C245") (pin "1") (pinfunction "1_1") (pintype "passive"))
      (node (ref "C246") (pin "1") (pinfunction "1_1") (pintype "passive"))
      (node (ref "C247") (pin "1") (pinfunction "1_1") (pintype "passive"))
      (node (ref "C248") (pin "1") (pinfunction "1_1") (pintype "passive"))
      (node (ref "C250") (pin "2") (pinfunction "2_2") (pintype "passive"))
      (node (ref "C251") (pin "2") (pinfunction "2_2") (pintype "passive"))
      (node (ref "C252") (pin "2") (pinfunction "2_2") (pintype "passive"))
      (node (ref "C253") (pin "1") (pinfunction "1_1") (pintype "passive"))
      (node (ref "C255") (pin "2") (pinfunction "2_2") (pintype "passive"))
      (node (ref "C256") (pin "1") (pinfunction "1_1") (pintype "passive"))
      (node (ref "C257") (pin "1") (pinfunction "1_1") (pintype "passive"))
      (node (ref "C258") (pin "1") (pinfunction "1_1") (pintype "passive"))
      (node (ref "C259") (pin "1") (pinfunction "1_1") (pintype "passive"))
      (node (ref "C261") (pin "1") (pinfunction "1_1") (pintype "passive"))
      (node (ref "C262") (pin "1") (pinfunction "1_1") (pintype "passive"))
      (node (ref "C263") (pin "1") (pinfunction "1_1") (pintype "passive"))
      (node (ref "C264") (pin "1") (pinfunction "1_1") (pintype "passive"))
      (node (ref "C266") (pin "1") (pinfunction "1_1") (pintype "passive"))
      (node (ref "C267") (pin "1") (pinfunction "1_1") (pintype "passive"))
      (node (ref "C268") (pin "1") (pinfunction "1_1") (pintype "passive"))
      (node (ref "C269") (pin "1") (pinfunction "1_1") (pintype "passive"))
      (node (ref "C270") (pin "1") (pinfunction "1_1") (pintype "passive"))
      (node (ref "C271") (pin "1") (pinfunction "1_1") (pintype "passive"))
      (node (ref "C272") (pin "1") (pinfunction "1_1") (pintype "passive"))
      (node (ref "C273") (pin "1") (pinfunction "1_1") (pintype "passive"))
      (node (ref "C275") (pin "2") (pinfunction "2_2") (pintype "passive"))
      (node (ref "C276") (pin "2") (pinfunction "2_2") (pintype "passive"))
      (node (ref "C277") (pin "2") (pinfunction "2_2") (pintype "passive"))
      (node (ref "C278") (pin "1") (pinfunction "1_1") (pintype "passive"))
      (node (ref "IC7") (pin "A1") (pinfunction "VDD_A1") (pintype "power_in"))
      (node (ref "IC7") (pin "A9") (pinfunction "VDDQ_A9") (pintype "power_in"))
      (node (ref "IC7") (pin "C1") (pinfunction "VDDQ_C1") (pintype "power_in"))
      (node (ref "IC7") (pin "C3") (pinfunction "VDDQ_C3") (pintype "power_in"))
      (node (ref "IC7") (pin "C7") (pinfunction "VDDQ_C7") (pintype "power_in"))
      (node (ref "IC7") (pin "C9") (pinfunction "VDDQ_C9") (pintype "power_in"))
      (node (ref "IC7") (pin "E1") (pinfunction "VDD_E1") (pintype "power_in"))
      (node (ref "IC7") (pin "E9") (pinfunction "VDDQ_E9") (pintype "power_in"))
      (node (ref "IC7") (pin "G1") (pinfunction "VDDQ_G1") (pintype "power_in"))
      (node (ref "IC7") (pin "G3") (pinfunction "VDDQ_G3") (pintype "power_in"))
      (node (ref "IC7") (pin "G7") (pinfunction "VDDQ_G7") (pintype "power_in"))
      (node (ref "IC7") (pin "G9") (pinfunction "VDDQ_G9") (pintype "power_in"))
      (node (ref "IC7") (pin "J1") (pinfunction "VDDL_J1") (pintype "power_in"))
      (node (ref "IC7") (pin "J9") (pinfunction "VDD_J9") (pintype "power_in"))
      (node (ref "IC7") (pin "M9") (pinfunction "VDD_M9") (pintype "power_in"))
      (node (ref "IC7") (pin "R1") (pinfunction "VDD_R1") (pintype "power_in"))
      (node (ref "IC8") (pin "A1") (pinfunction "VDD_A1") (pintype "power_in"))
      (node (ref "IC8") (pin "A9") (pinfunction "VDDQ_A9") (pintype "power_in"))
      (node (ref "IC8") (pin "C1") (pinfunction "VDDQ_C1") (pintype "power_in"))
      (node (ref "IC8") (pin "C3") (pinfunction "VDDQ_C3") (pintype "power_in"))
      (node (ref "IC8") (pin "C7") (pinfunction "VDDQ_C7") (pintype "power_in"))
      (node (ref "IC8") (pin "C9") (pinfunction "VDDQ_C9") (pintype "power_in"))
      (node (ref "IC8") (pin "E1") (pinfunction "VDD_E1") (pintype "power_in"))
      (node (ref "IC8") (pin "E9") (pinfunction "VDDQ_E9") (pintype "power_in"))
      (node (ref "IC8") (pin "G1") (pinfunction "VDDQ_G1") (pintype "power_in"))
      (node (ref "IC8") (pin "G3") (pinfunction "VDDQ_G3") (pintype "power_in"))
      (node (ref "IC8") (pin "G7") (pinfunction "VDDQ_G7") (pintype "power_in"))
      (node (ref "IC8") (pin "G9") (pinfunction "VDDQ_G9") (pintype "power_in"))
      (node (ref "IC8") (pin "J1") (pinfunction "VDDL_J1") (pintype "power_in"))
      (node (ref "IC8") (pin "J9") (pinfunction "VDD_J9") (pintype "power_in"))
      (node (ref "IC8") (pin "M9") (pinfunction "VDD_M9") (pintype "power_in"))
      (node (ref "IC8") (pin "R1") (pinfunction "VDD_R1") (pintype "power_in"))
    )
    (net (code "106") (name "VTT_DDR2") (class "Default")
      (node (ref "C235") (pin "1") (pinfunction "1_1") (pintype "passive"))
      (node (ref "C235") (pin "2") (pinfunction "2_2") (pintype "passive"))
      (node (ref "C235") (pin "3") (pinfunction "3_3") (pintype "passive"))
      (node (ref "C235") (pin "4") (pinfunction "4_4") (pintype "passive"))
      (node (ref "C244") (pin "1") (pinfunction "1_1") (pintype "passive"))
      (node (ref "C244") (pin "2") (pinfunction "2_2") (pintype "passive"))
      (node (ref "C244") (pin "3") (pinfunction "3_3") (pintype "passive"))
      (node (ref "C244") (pin "4") (pinfunction "4_4") (pintype "passive"))
      (node (ref "C249") (pin "1") (pinfunction "1_1") (pintype "passive"))
      (node (ref "C249") (pin "2") (pinfunction "2_2") (pintype "passive"))
      (node (ref "C249") (pin "3") (pinfunction "3_3") (pintype "passive"))
      (node (ref "C249") (pin "4") (pinfunction "4_4") (pintype "passive"))
      (node (ref "C260") (pin "1") (pinfunction "1_1") (pintype "passive"))
      (node (ref "C260") (pin "2") (pinfunction "2_2") (pintype "passive"))
      (node (ref "C260") (pin "3") (pinfunction "3_3") (pintype "passive"))
      (node (ref "C260") (pin "4") (pinfunction "4_4") (pintype "passive"))
      (node (ref "C265") (pin "1") (pinfunction "1_1") (pintype "passive"))
      (node (ref "C265") (pin "2") (pinfunction "2_2") (pintype "passive"))
      (node (ref "C265") (pin "3") (pinfunction "3_3") (pintype "passive"))
      (node (ref "C265") (pin "4") (pinfunction "4_4") (pintype "passive"))
      (node (ref "C274") (pin "1") (pinfunction "1_1") (pintype "passive"))
      (node (ref "C274") (pin "2") (pinfunction "2_2") (pintype "passive"))
      (node (ref "C274") (pin "3") (pinfunction "3_3") (pintype "passive"))
      (node (ref "C274") (pin "4") (pinfunction "4_4") (pintype "passive"))
      (node (ref "R62") (pin "10") (pinfunction "10_10") (pintype "passive"))
      (node (ref "R62") (pin "11") (pinfunction "11_11") (pintype "passive"))
      (node (ref "R62") (pin "12") (pinfunction "12_12") (pintype "passive"))
      (node (ref "R62") (pin "13") (pinfunction "13_13") (pintype "passive"))
      (node (ref "R62") (pin "14") (pinfunction "14_14") (pintype "passive"))
      (node (ref "R62") (pin "15") (pinfunction "15_15") (pintype "passive"))
      (node (ref "R62") (pin "16") (pinfunction "16_16") (pintype "passive"))
      (node (ref "R62") (pin "9") (pinfunction "9_9") (pintype "passive"))
      (node (ref "R64") (pin "10") (pinfunction "10_10") (pintype "passive"))
      (node (ref "R64") (pin "11") (pinfunction "11_11") (pintype "passive"))
      (node (ref "R64") (pin "12") (pinfunction "12_12") (pintype "passive"))
      (node (ref "R64") (pin "13") (pinfunction "13_13") (pintype "passive"))
      (node (ref "R64") (pin "14") (pinfunction "14_14") (pintype "passive"))
      (node (ref "R64") (pin "15") (pinfunction "15_15") (pintype "passive"))
      (node (ref "R64") (pin "16") (pinfunction "16_16") (pintype "passive"))
      (node (ref "R64") (pin "9") (pinfunction "9_9") (pintype "passive"))
      (node (ref "R65") (pin "10") (pinfunction "10_10") (pintype "passive"))
      (node (ref "R65") (pin "11") (pinfunction "11_11") (pintype "passive"))
      (node (ref "R65") (pin "12") (pinfunction "12_12") (pintype "passive"))
      (node (ref "R65") (pin "13") (pinfunction "13_13") (pintype "passive"))
      (node (ref "R65") (pin "14") (pinfunction "14_14") (pintype "passive"))
      (node (ref "R65") (pin "15") (pinfunction "15_15") (pintype "passive"))
      (node (ref "R65") (pin "16") (pinfunction "16_16") (pintype "passive"))
      (node (ref "R65") (pin "9") (pinfunction "9_9") (pintype "passive"))
      (node (ref "R68") (pin "10") (pinfunction "10_10") (pintype "passive"))
      (node (ref "R68") (pin "11") (pinfunction "11_11") (pintype "passive"))
      (node (ref "R68") (pin "12") (pinfunction "12_12") (pintype "passive"))
      (node (ref "R68") (pin "13") (pinfunction "13_13") (pintype "passive"))
      (node (ref "R68") (pin "14") (pinfunction "14_14") (pintype "passive"))
      (node (ref "R68") (pin "15") (pinfunction "15_15") (pintype "passive"))
      (node (ref "R68") (pin "16") (pinfunction "16_16") (pintype "passive"))
      (node (ref "R68") (pin "9") (pinfunction "9_9") (pintype "passive"))
      (node (ref "R70") (pin "10") (pinfunction "10_10") (pintype "passive"))
      (node (ref "R70") (pin "11") (pinfunction "11_11") (pintype "passive"))
      (node (ref "R70") (pin "12") (pinfunction "12_12") (pintype "passive"))
      (node (ref "R70") (pin "13") (pinfunction "13_13") (pintype "passive"))
      (node (ref "R70") (pin "14") (pinfunction "14_14") (pintype "passive"))
      (node (ref "R70") (pin "15") (pinfunction "15_15") (pintype "passive"))
      (node (ref "R70") (pin "16") (pinfunction "16_16") (pintype "passive"))
      (node (ref "R70") (pin "9") (pinfunction "9_9") (pintype "passive"))
      (node (ref "R71") (pin "10") (pinfunction "10_10") (pintype "passive"))
      (node (ref "R71") (pin "11") (pinfunction "11_11") (pintype "passive"))
      (node (ref "R71") (pin "12") (pinfunction "12_12") (pintype "passive"))
      (node (ref "R71") (pin "13") (pinfunction "13_13") (pintype "passive"))
      (node (ref "R71") (pin "14") (pinfunction "14_14") (pintype "passive"))
      (node (ref "R71") (pin "15") (pinfunction "15_15") (pintype "passive"))
      (node (ref "R71") (pin "16") (pinfunction "16_16") (pintype "passive"))
      (node (ref "R71") (pin "9") (pinfunction "9_9") (pintype "passive"))
    )
    (net (code "107") (name "unconnected-(IC7B-NC-PadA2)") (class "Default")
      (node (ref "IC7") (pin "A2") (pinfunction "NC_A2") (pintype "passive+no_connect"))
    )
    (net (code "108") (name "unconnected-(IC7B-NC-PadE2)") (class "Default")
      (node (ref "IC7") (pin "E2") (pinfunction "NC_E2") (pintype "passive+no_connect"))
    )
    (net (code "109") (name "unconnected-(IC7B-NC-PadR3)") (class "Default")
      (node (ref "IC7") (pin "R3") (pinfunction "NC_R3") (pintype "passive+no_connect"))
    )
    (net (code "110") (name "unconnected-(IC7B-NC-PadR7)") (class "Default")
      (node (ref "IC7") (pin "R7") (pinfunction "NC_R7") (pintype "passive+no_connect"))
    )
    (net (code "111") (name "unconnected-(IC7B-NC-PadR8)") (class "Default")
      (node (ref "IC7") (pin "R8") (pinfunction "NC_R8") (pintype "passive+no_connect"))
    )
    (net (code "112") (name "unconnected-(IC8B-NC-PadA2)") (class "Default")
      (node (ref "IC8") (pin "A2") (pinfunction "NC_A2") (pintype "passive+no_connect"))
    )
    (net (code "113") (name "unconnected-(IC8B-NC-PadE2)") (class "Default")
      (node (ref "IC8") (pin "E2") (pinfunction "NC_E2") (pintype "passive+no_connect"))
    )
    (net (code "114") (name "unconnected-(IC8B-NC-PadR3)") (class "Default")
      (node (ref "IC8") (pin "R3") (pinfunction "NC_R3") (pintype "passive+no_connect"))
    )
    (net (code "115") (name "unconnected-(IC8B-NC-PadR7)") (class "Default")
      (node (ref "IC8") (pin "R7") (pinfunction "NC_R7") (pintype "passive+no_connect"))
    )
    (net (code "116") (name "unconnected-(IC8B-NC-PadR8)") (class "Default")
      (node (ref "IC8") (pin "R8") (pinfunction "NC_R8") (pintype "passive+no_connect"))
    )
    (net (code "117") (name "unconnected-(R64-Pad1)") (class "Default")
      (node (ref "R64") (pin "1") (pinfunction "1_1") (pintype "passive+no_connect"))
    )
    (net (code "118") (name "unconnected-(R65-Pad1)") (class "Default")
      (node (ref "R65") (pin "1") (pinfunction "1_1") (pintype "passive+no_connect"))
    )
    (net (code "119") (name "unconnected-(R70-Pad1)") (class "Default")
      (node (ref "R70") (pin "1") (pinfunction "1_1") (pintype "passive+no_connect"))
    )
    (net (code "120") (name "unconnected-(R71-Pad8)") (class "Default")
      (node (ref "R71") (pin "8") (pinfunction "8_8") (pintype "passive+no_connect"))
    )
  )
)
